# PIC32.net
KiCad netlist of a schematic drawn in Altium Designer
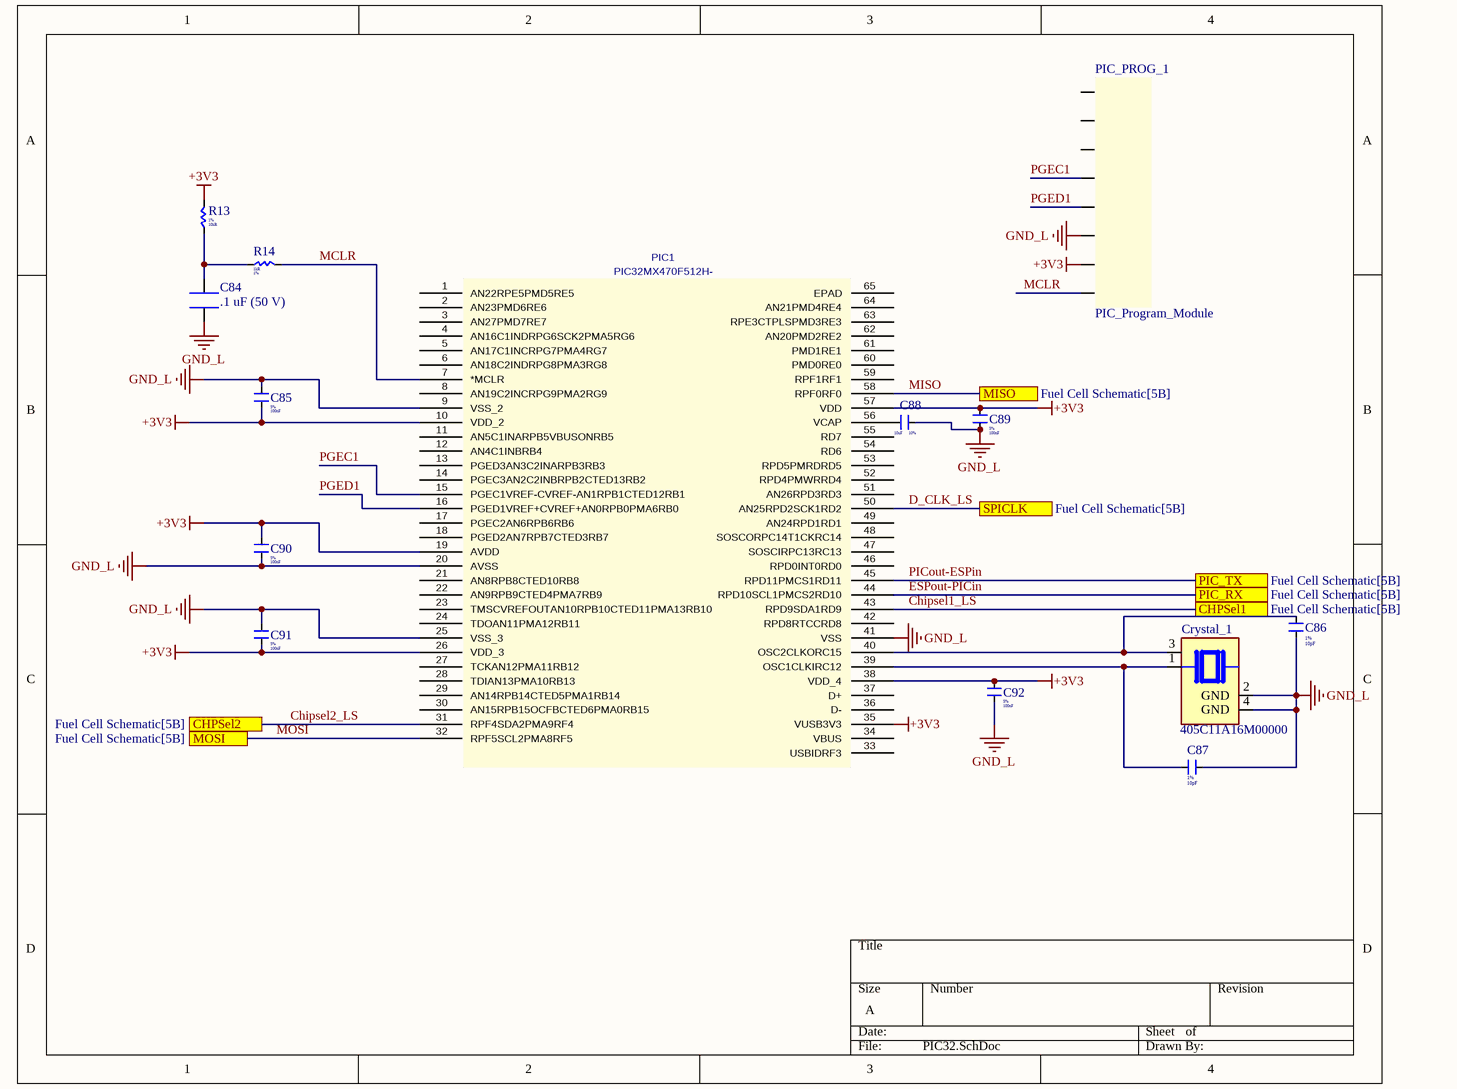
[diagram p0: PIC32.SchDoc]

(export (version "E")
  (design (tool "Eeschema 10.0.6"))
  (components
    (comp (ref "C84")
      (value ".1 uF (50 V)")
      (footprint ".1uF capacitor")
      (libsource (lib "Schlib1") (part ".1 uF cap"))
    )
    (comp (ref "C85")
      (value "~")
      (footprint "Capacitor_Kemet_0805")
      (description "Cap Ceramic 0.1uF 16V X7R 5% SMD 0805 125°C Plastic T/R")
      (fields
        (field (name "MANUFACTURER") "KEMET")
        (field (name "MANUFACTURER PART NUMBER") "C0805C104J4RACTU")
        (field (name "DISSIPATION FACTOR") "5%")
        (field (name "CAPACITANCE") "100nF")
      )
      (libsource (lib "Schlib1") (part "C0805C104J4RACTU"))
    )
    (comp (ref "C86")
      (value "~")
      (footprint "Kemet_10pF_0805")
      (description "Cap, AEC-Q200, 10PF, 50V, Mlcc, 0805;")
      (fields
        (field (name "MANUFACTURER") "KEMET")
        (field (name "MANUFACTURER PART NUMBER") "C0805C100F5GACAUTO")
        (field (name "TOLLERANCE") "1%")
        (field (name "CAPACITANCE") "10pF")
      )
      (libsource (lib "Schlib1") (part "C0805C100F5GACAUTO"))
    )
    (comp (ref "C87")
      (value "~")
      (footprint "Kemet_10pF_0805")
      (description "Cap, AEC-Q200, 10PF, 50V, Mlcc, 0805;")
      (fields
        (field (name "MANUFACTURER") "KEMET")
        (field (name "MANUFACTURER PART NUMBER") "C0805C100F5GACAUTO")
        (field (name "TOLLERANCE") "1%")
        (field (name "CAPACITANCE") "10pF")
      )
      (libsource (lib "Schlib1") (part "C0805C100F5GACAUTO"))
    )
    (comp (ref "C88")
      (value "~")
      (footprint "Capacitor_Kemet_0805")
      (description "0805 C 10uF Ceramic Multilayer Capacitor; 25 VDC; +85degC; X5R Dielec; +/-10%")
      (fields
        (field (name "MANUFACTURER") "KEMET")
        (field (name "MANUFACTURER PART NUMBER") "C0805C106K3PACTU")
        (field (name "DISSIPATION FACTOR") "10%")
        (field (name "CAPACITANCE") "10uF")
      )
      (libsource (lib "Schlib1") (part "C0805C106K3PACTU"))
    )
    (comp (ref "C89")
      (value "~")
      (footprint "Capacitor_Kemet_0805")
      (description "Cap Ceramic 0.1uF 16V X7R 5% SMD 0805 125°C Plastic T/R")
      (fields
        (field (name "MANUFACTURER") "KEMET")
        (field (name "MANUFACTURER PART NUMBER") "C0805C104J4RACTU")
        (field (name "DISSIPATION FACTOR") "5%")
        (field (name "CAPACITANCE") "100nF")
      )
      (libsource (lib "Schlib1") (part "C0805C104J4RACTU"))
    )
    (comp (ref "C90")
      (value "~")
      (footprint "Capacitor_Kemet_0805")
      (description "Cap Ceramic 0.1uF 16V X7R 5% SMD 0805 125°C Plastic T/R")
      (fields
        (field (name "MANUFACTURER") "KEMET")
        (field (name "MANUFACTURER PART NUMBER") "C0805C104J4RACTU")
        (field (name "DISSIPATION FACTOR") "5%")
        (field (name "CAPACITANCE") "100nF")
      )
      (libsource (lib "Schlib1") (part "C0805C104J4RACTU"))
    )
    (comp (ref "C91")
      (value "~")
      (footprint "Capacitor_Kemet_0805")
      (description "Cap Ceramic 0.1uF 16V X7R 5% SMD 0805 125°C Plastic T/R")
      (fields
        (field (name "MANUFACTURER") "KEMET")
        (field (name "MANUFACTURER PART NUMBER") "C0805C104J4RACTU")
        (field (name "DISSIPATION FACTOR") "5%")
        (field (name "CAPACITANCE") "100nF")
      )
      (libsource (lib "Schlib1") (part "C0805C104J4RACTU"))
    )
    (comp (ref "C92")
      (value "~")
      (footprint "Capacitor_Kemet_0805")
      (description "Cap Ceramic 0.1uF 16V X7R 5% SMD 0805 125°C Plastic T/R")
      (fields
        (field (name "MANUFACTURER") "KEMET")
        (field (name "MANUFACTURER PART NUMBER") "C0805C104J4RACTU")
        (field (name "DISSIPATION FACTOR") "5%")
        (field (name "CAPACITANCE") "100nF")
      )
      (libsource (lib "Schlib1") (part "C0805C104J4RACTU"))
    )
    (comp (ref "Crystal_1")
      (value "405C11A16M00000")
      (footprint "XTAL_405C11A16M00000")
      (description "CRYSTAL 16.0000MHZ 10PF SMD")
      (fields
        (field (name "DIGI-KEY_PART_NUMBER") "CTX834TR-ND")
        (field (name "MF") "CTS-Frequency Controls")
      )
      (libsource (lib "Schlib1") (part "405C11A16M00000"))
    )
    (comp (ref "PIC1")
      (value "PIC32MX470F512H-")
      (footprint "Quad64_2")
      (fields
        (field (name "MANUFACTURER_PART_NUMBER") "PIC32MX470F512H-I/MR")
        (field (name "COPYRIGHT") "Copyright (C) 2023 Ultra Librarian. All rights reserved.")
      )
      (libsource (lib "Schlib1") (part "PIC32MX470F512H-"))
    )
    (comp (ref "PIC_PROG_1")
      (value "PIC_Program_Module")
      (footprint "PIC_32_POD")
      (libsource (lib "Schlib1") (part "PIC_Program_Module"))
    )
    (comp (ref "R13")
      (value "~")
      (footprint "Resistor_YAGEO_0805")
      (description "RES 10K OHM 1% 1/8W 0805")
      (fields
        (field (name "MANUFACTURER") "Yageo")
        (field (name "MANUFACTURER PART NUMBER") "RC0805FR-1010KL")
        (field (name "TOLERANCE") "1%")
        (field (name "RESISTANCE") "10kR")
      )
      (libsource (lib "Schlib1") (part "RC0805FR-1010KL"))
    )
    (comp (ref "R14")
      (value "~")
      (footprint "Resistor_YAGEO_0805")
      (description "Res Thick Film 0805 1K Ohm 1% 0.125W(1/8W) ±100ppm/C Pad SMD T/R")
      (fields
        (field (name "MANUFACTURER") "Yageo")
        (field (name "MANUFACTURER PART NUMBER") "RC0805FR-071KP")
        (field (name "RESISTANCE") "1kR")
        (field (name "TOLERANCE") "1%")
      )
      (libsource (lib "Schlib1") (part "RC0805FR-071KP"))
    )
  )
  (nets
    (net (code "1") (name "+3V3") (class "Default")
      (node (ref "C85") (pin "1") (pinfunction "1_1") (pintype "passive"))
      (node (ref "C89") (pin "2") (pinfunction "2_2") (pintype "passive"))
      (node (ref "C90") (pin "2") (pinfunction "2_2") (pintype "passive"))
      (node (ref "C91") (pin "1") (pinfunction "1_1") (pintype "passive"))
      (node (ref "C92") (pin "2") (pinfunction "2_2") (pintype "passive"))
      (node (ref "PIC1") (pin "10") (pinfunction "VDD_2_10") (pintype "passive"))
      (node (ref "PIC1") (pin "19") (pinfunction "AVDD_19") (pintype "passive"))
      (node (ref "PIC1") (pin "26") (pinfunction "VDD_3_26") (pintype "passive"))
      (node (ref "PIC1") (pin "35") (pinfunction "VUSB3V3_35") (pintype "passive"))
      (node (ref "PIC1") (pin "38") (pinfunction "VDD_4_38") (pintype "passive"))
      (node (ref "PIC1") (pin "57") (pinfunction "VDD_57") (pintype "passive"))
      (node (ref "PIC_PROG_1") (pin "2") (pinfunction "VDD_2") (pintype "passive"))
      (node (ref "R13") (pin "2") (pinfunction "2_2") (pintype "passive"))
    )
    (net (code "2") (name "/Chipsel1_LS") (class "Default")
      (node (ref "PIC1") (pin "43") (pinfunction "RPD9SDA1RD9_43") (pintype "passive"))
    )
    (net (code "3") (name "/Chipsel2_LS") (class "Default")
      (node (ref "PIC1") (pin "31") (pinfunction "RPF4SDA2PMA9RF4_31") (pintype "passive"))
    )
    (net (code "4") (name "/D_CLK_LS") (class "Default")
      (node (ref "PIC1") (pin "50") (pinfunction "AN25RPD2SCK1RD2_50") (pintype "passive"))
    )
    (net (code "5") (name "/ESPout-PICin") (class "Default")
      (node (ref "PIC1") (pin "44") (pinfunction "RPD10SCL1PMCS2RD10_44") (pintype "passive"))
    )
    (net (code "6") (name "/MCLR") (class "Default")
      (node (ref "PIC1") (pin "7") (pinfunction "*MCLR_7") (pintype "passive"))
      (node (ref "PIC_PROG_1") (pin "1") (pinfunction "MCLR_1") (pintype "passive"))
      (node (ref "R14") (pin "2") (pinfunction "2_2") (pintype "passive"))
    )
    (net (code "7") (name "/MISO") (class "Default")
      (node (ref "PIC1") (pin "58") (pinfunction "RPF0RF0_58") (pintype "passive"))
    )
    (net (code "8") (name "/MOSI") (class "Default")
      (node (ref "PIC1") (pin "32") (pinfunction "RPF5SCL2PMA8RF5_32") (pintype "passive"))
    )
    (net (code "9") (name "/PGEC1") (class "Default")
      (node (ref "PIC1") (pin "15") (pinfunction "PGEC1VREF-CVREF-AN1RPB1CTED12RB1_15") (pintype "passive"))
      (node (ref "PIC_PROG_1") (pin "5") (pinfunction "PGEC_5") (pintype "passive"))
    )
    (net (code "10") (name "/PGED1") (class "Default")
      (node (ref "PIC1") (pin "16") (pinfunction "PGED1VREF+CVREF+AN0RPB0PMA6RB0_16") (pintype "passive"))
      (node (ref "PIC_PROG_1") (pin "4") (pinfunction "PGED_4") (pintype "passive"))
    )
    (net (code "11") (name "/PICout-ESPin") (class "Default")
      (node (ref "PIC1") (pin "45") (pinfunction "RPD11PMCS1RD11_45") (pintype "passive"))
    )
    (net (code "12") (name "GND_L") (class "Default")
      (node (ref "C84") (pin "2") (pinfunction "2_2") (pintype "passive"))
      (node (ref "C85") (pin "2") (pinfunction "2_2") (pintype "passive"))
      (node (ref "C86") (pin "2") (pinfunction "2_2") (pintype "passive"))
      (node (ref "C87") (pin "1") (pinfunction "1_1") (pintype "passive"))
      (node (ref "C88") (pin "2") (pinfunction "2_2") (pintype "passive"))
      (node (ref "C89") (pin "1") (pinfunction "1_1") (pintype "passive"))
      (node (ref "C90") (pin "1") (pinfunction "1_1") (pintype "passive"))
      (node (ref "C91") (pin "2") (pinfunction "2_2") (pintype "passive"))
      (node (ref "C92") (pin "1") (pinfunction "1_1") (pintype "passive"))
      (node (ref "Crystal_1") (pin "2") (pinfunction "GND_2") (pintype "power_in"))
      (node (ref "Crystal_1") (pin "4") (pinfunction "GND_4") (pintype "power_in"))
      (node (ref "PIC1") (pin "20") (pinfunction "AVSS_20") (pintype "passive"))
      (node (ref "PIC1") (pin "25") (pinfunction "VSS_3_25") (pintype "passive"))
      (node (ref "PIC1") (pin "41") (pinfunction "VSS_41") (pintype "passive"))
      (node (ref "PIC1") (pin "9") (pinfunction "VSS_2_9") (pintype "passive"))
      (node (ref "PIC_PROG_1") (pin "3") (pinfunction "GND_3") (pintype "passive"))
    )
    (net (code "13") (name "Net-(C84-Pad1)") (class "Default")
      (node (ref "C84") (pin "1") (pinfunction "1_1") (pintype "passive"))
      (node (ref "R13") (pin "1") (pinfunction "1_1") (pintype "passive"))
      (node (ref "R14") (pin "1") (pinfunction "1_1") (pintype "passive"))
    )
    (net (code "14") (name "Net-(Crystal_1-2)") (class "Default")
      (node (ref "C86") (pin "1") (pinfunction "1_1") (pintype "passive"))
      (node (ref "Crystal_1") (pin "3") (pinfunction "2_3") (pintype "passive"))
      (node (ref "PIC1") (pin "40") (pinfunction "OSC2CLKORC15_40") (pintype "passive"))
    )
    (net (code "15") (name "Net-(PIC1-OSC1CLKIRC12)") (class "Default")
      (node (ref "C87") (pin "2") (pinfunction "2_2") (pintype "passive"))
      (node (ref "Crystal_1") (pin "1") (pinfunction "1_1") (pintype "passive"))
      (node (ref "PIC1") (pin "39") (pinfunction "OSC1CLKIRC12_39") (pintype "passive"))
    )
    (net (code "16") (name "Net-(PIC1-VCAP)") (class "Default")
      (node (ref "C88") (pin "1") (pinfunction "1_1") (pintype "passive"))
      (node (ref "PIC1") (pin "56") (pinfunction "VCAP_56") (pintype "passive"))
    )
    (net (code "17") (name "unconnected-(PIC1-AN4C1INBRB4-Pad12)") (class "Default")
      (node (ref "PIC1") (pin "12") (pinfunction "AN4C1INBRB4_12") (pintype "passive"))
    )
    (net (code "18") (name "unconnected-(PIC1-AN5C1INARPB5VBUSONRB5-Pad11)") (class "Default")
      (node (ref "PIC1") (pin "11") (pinfunction "AN5C1INARPB5VBUSONRB5_11") (pintype "passive"))
    )
    (net (code "19") (name "unconnected-(PIC1-AN8RPB8CTED10RB8-Pad21)") (class "Default")
      (node (ref "PIC1") (pin "21") (pinfunction "AN8RPB8CTED10RB8_21") (pintype "passive"))
    )
    (net (code "20") (name "unconnected-(PIC1-AN9RPB9CTED4PMA7RB9-Pad22)") (class "Default")
      (node (ref "PIC1") (pin "22") (pinfunction "AN9RPB9CTED4PMA7RB9_22") (pintype "passive"))
    )
    (net (code "21") (name "unconnected-(PIC1-AN14RPB14CTED5PMA1RB14-Pad29)") (class "Default")
      (node (ref "PIC1") (pin "29") (pinfunction "AN14RPB14CTED5PMA1RB14_29") (pintype "passive"))
    )
    (net (code "22") (name "unconnected-(PIC1-AN15RPB15OCFBCTED6PMA0RB15-Pad30)") (class "Default")
      (node (ref "PIC1") (pin "30") (pinfunction "AN15RPB15OCFBCTED6PMA0RB15_30") (pintype "passive"))
    )
    (net (code "23") (name "unconnected-(PIC1-AN16C1INDRPG6SCK2PMA5RG6-Pad4)") (class "Default")
      (node (ref "PIC1") (pin "4") (pinfunction "AN16C1INDRPG6SCK2PMA5RG6_4") (pintype "passive"))
    )
    (net (code "24") (name "unconnected-(PIC1-AN17C1INCRPG7PMA4RG7-Pad5)") (class "Default")
      (node (ref "PIC1") (pin "5") (pinfunction "AN17C1INCRPG7PMA4RG7_5") (pintype "passive"))
    )
    (net (code "25") (name "unconnected-(PIC1-AN18C2INDRPG8PMA3RG8-Pad6)") (class "Default")
      (node (ref "PIC1") (pin "6") (pinfunction "AN18C2INDRPG8PMA3RG8_6") (pintype "passive"))
    )
    (net (code "26") (name "unconnected-(PIC1-AN19C2INCRPG9PMA2RG9-Pad8)") (class "Default")
      (node (ref "PIC1") (pin "8") (pinfunction "AN19C2INCRPG9PMA2RG9_8") (pintype "passive"))
    )
    (net (code "27") (name "unconnected-(PIC1-AN20PMD2RE2-Pad62)") (class "Default")
      (node (ref "PIC1") (pin "62") (pinfunction "AN20PMD2RE2_62") (pintype "passive"))
    )
    (net (code "28") (name "unconnected-(PIC1-AN21PMD4RE4-Pad64)") (class "Default")
      (node (ref "PIC1") (pin "64") (pinfunction "AN21PMD4RE4_64") (pintype "passive"))
    )
    (net (code "29") (name "unconnected-(PIC1-AN22RPE5PMD5RE5-Pad1)") (class "Default")
      (node (ref "PIC1") (pin "1") (pinfunction "AN22RPE5PMD5RE5_1") (pintype "passive"))
    )
    (net (code "30") (name "unconnected-(PIC1-AN23PMD6RE6-Pad2)") (class "Default")
      (node (ref "PIC1") (pin "2") (pinfunction "AN23PMD6RE6_2") (pintype "passive"))
    )
    (net (code "31") (name "unconnected-(PIC1-AN24RPD1RD1-Pad49)") (class "Default")
      (node (ref "PIC1") (pin "49") (pinfunction "AN24RPD1RD1_49") (pintype "passive"))
    )
    (net (code "32") (name "unconnected-(PIC1-AN26RPD3RD3-Pad51)") (class "Default")
      (node (ref "PIC1") (pin "51") (pinfunction "AN26RPD3RD3_51") (pintype "passive"))
    )
    (net (code "33") (name "unconnected-(PIC1-AN27PMD7RE7-Pad3)") (class "Default")
      (node (ref "PIC1") (pin "3") (pinfunction "AN27PMD7RE7_3") (pintype "passive"))
    )
    (net (code "34") (name "unconnected-(PIC1-D+-Pad37)") (class "Default")
      (node (ref "PIC1") (pin "37") (pinfunction "D+_37") (pintype "passive"))
    )
    (net (code "35") (name "unconnected-(PIC1-D--Pad36)") (class "Default")
      (node (ref "PIC1") (pin "36") (pinfunction "D-_36") (pintype "passive"))
    )
    (net (code "36") (name "unconnected-(PIC1-EPAD-Pad65)") (class "Default")
      (node (ref "PIC1") (pin "65") (pinfunction "EPAD_65") (pintype "passive"))
    )
    (net (code "37") (name "unconnected-(PIC1-PGEC2AN6RPB6RB6-Pad17)") (class "Default")
      (node (ref "PIC1") (pin "17") (pinfunction "PGEC2AN6RPB6RB6_17") (pintype "passive"))
    )
    (net (code "38") (name "unconnected-(PIC1-PGEC3AN2C2INBRPB2CTED13RB2-Pad14)") (class "Default")
      (node (ref "PIC1") (pin "14") (pinfunction "PGEC3AN2C2INBRPB2CTED13RB2_14") (pintype "passive"))
    )
    (net (code "39") (name "unconnected-(PIC1-PGED2AN7RPB7CTED3RB7-Pad18)") (class "Default")
      (node (ref "PIC1") (pin "18") (pinfunction "PGED2AN7RPB7CTED3RB7_18") (pintype "passive"))
    )
    (net (code "40") (name "unconnected-(PIC1-PGED3AN3C2INARPB3RB3-Pad13)") (class "Default")
      (node (ref "PIC1") (pin "13") (pinfunction "PGED3AN3C2INARPB3RB3_13") (pintype "passive"))
    )
    (net (code "41") (name "unconnected-(PIC1-PMD0RE0-Pad60)") (class "Default")
      (node (ref "PIC1") (pin "60") (pinfunction "PMD0RE0_60") (pintype "passive"))
    )
    (net (code "42") (name "unconnected-(PIC1-PMD1RE1-Pad61)") (class "Default")
      (node (ref "PIC1") (pin "61") (pinfunction "PMD1RE1_61") (pintype "passive"))
    )
    (net (code "43") (name "unconnected-(PIC1-RD6-Pad54)") (class "Default")
      (node (ref "PIC1") (pin "54") (pinfunction "RD6_54") (pintype "passive"))
    )
    (net (code "44") (name "unconnected-(PIC1-RD7-Pad55)") (class "Default")
      (node (ref "PIC1") (pin "55") (pinfunction "RD7_55") (pintype "passive"))
    )
    (net (code "45") (name "unconnected-(PIC1-RPD0INT0RD0-Pad46)") (class "Default")
      (node (ref "PIC1") (pin "46") (pinfunction "RPD0INT0RD0_46") (pintype "passive"))
    )
    (net (code "46") (name "unconnected-(PIC1-RPD4PMWRRD4-Pad52)") (class "Default")
      (node (ref "PIC1") (pin "52") (pinfunction "RPD4PMWRRD4_52") (pintype "passive"))
    )
    (net (code "47") (name "unconnected-(PIC1-RPD5PMRDRD5-Pad53)") (class "Default")
      (node (ref "PIC1") (pin "53") (pinfunction "RPD5PMRDRD5_53") (pintype "passive"))
    )
    (net (code "48") (name "unconnected-(PIC1-RPD8RTCCRD8-Pad42)") (class "Default")
      (node (ref "PIC1") (pin "42") (pinfunction "RPD8RTCCRD8_42") (pintype "passive"))
    )
    (net (code "49") (name "unconnected-(PIC1-RPE3CTPLSPMD3RE3-Pad63)") (class "Default")
      (node (ref "PIC1") (pin "63") (pinfunction "RPE3CTPLSPMD3RE3_63") (pintype "passive"))
    )
    (net (code "50") (name "unconnected-(PIC1-RPF1RF1-Pad59)") (class "Default")
      (node (ref "PIC1") (pin "59") (pinfunction "RPF1RF1_59") (pintype "passive"))
    )
    (net (code "51") (name "unconnected-(PIC1-SOSCIRPC13RC13-Pad47)") (class "Default")
      (node (ref "PIC1") (pin "47") (pinfunction "SOSCIRPC13RC13_47") (pintype "passive"))
    )
    (net (code "52") (name "unconnected-(PIC1-SOSCORPC14T1CKRC14-Pad48)") (class "Default")
      (node (ref "PIC1") (pin "48") (pinfunction "SOSCORPC14T1CKRC14_48") (pintype "passive"))
    )
    (net (code "53") (name "unconnected-(PIC1-TCKAN12PMA11RB12-Pad27)") (class "Default")
      (node (ref "PIC1") (pin "27") (pinfunction "TCKAN12PMA11RB12_27") (pintype "passive"))
    )
    (net (code "54") (name "unconnected-(PIC1-TDIAN13PMA10RB13-Pad28)") (class "Default")
      (node (ref "PIC1") (pin "28") (pinfunction "TDIAN13PMA10RB13_28") (pintype "passive"))
    )
    (net (code "55") (name "unconnected-(PIC1-TDOAN11PMA12RB11-Pad24)") (class "Default")
      (node (ref "PIC1") (pin "24") (pinfunction "TDOAN11PMA12RB11_24") (pintype "passive"))
    )
    (net (code "56") (name "unconnected-(PIC1-TMSCVREFOUTAN10RPB10CTED11PMA13RB10-Pad23)") (class "Default")
      (node (ref "PIC1") (pin "23") (pinfunction "TMSCVREFOUTAN10RPB10CTED11PMA13RB10_23") (pintype "passive"))
    )
    (net (code "57") (name "unconnected-(PIC1-USBIDRF3-Pad33)") (class "Default")
      (node (ref "PIC1") (pin "33") (pinfunction "USBIDRF3_33") (pintype "passive"))
    )
    (net (code "58") (name "unconnected-(PIC1-VBUS-Pad34)") (class "Default")
      (node (ref "PIC1") (pin "34") (pinfunction "VBUS_34") (pintype "passive"))
    )
    (net (code "59") (name "unconnected-(PIC_PROG_1-Pad6)") (class "Default")
      (node (ref "PIC_PROG_1") (pin "6") (pinfunction "6_6") (pintype "passive"))
    )
    (net (code "60") (name "unconnected-(PIC_PROG_1-Pad7)") (class "Default")
      (node (ref "PIC_PROG_1") (pin "7") (pinfunction "7_7") (pintype "passive"))
    )
    (net (code "61") (name "unconnected-(PIC_PROG_1-Pad8)") (class "Default")
      (node (ref "PIC_PROG_1") (pin "8") (pinfunction "8_8") (pintype "passive"))
    )
  )
)
